# Microcontroller.net
KiCad netlist of a schematic drawn in Altium Designer
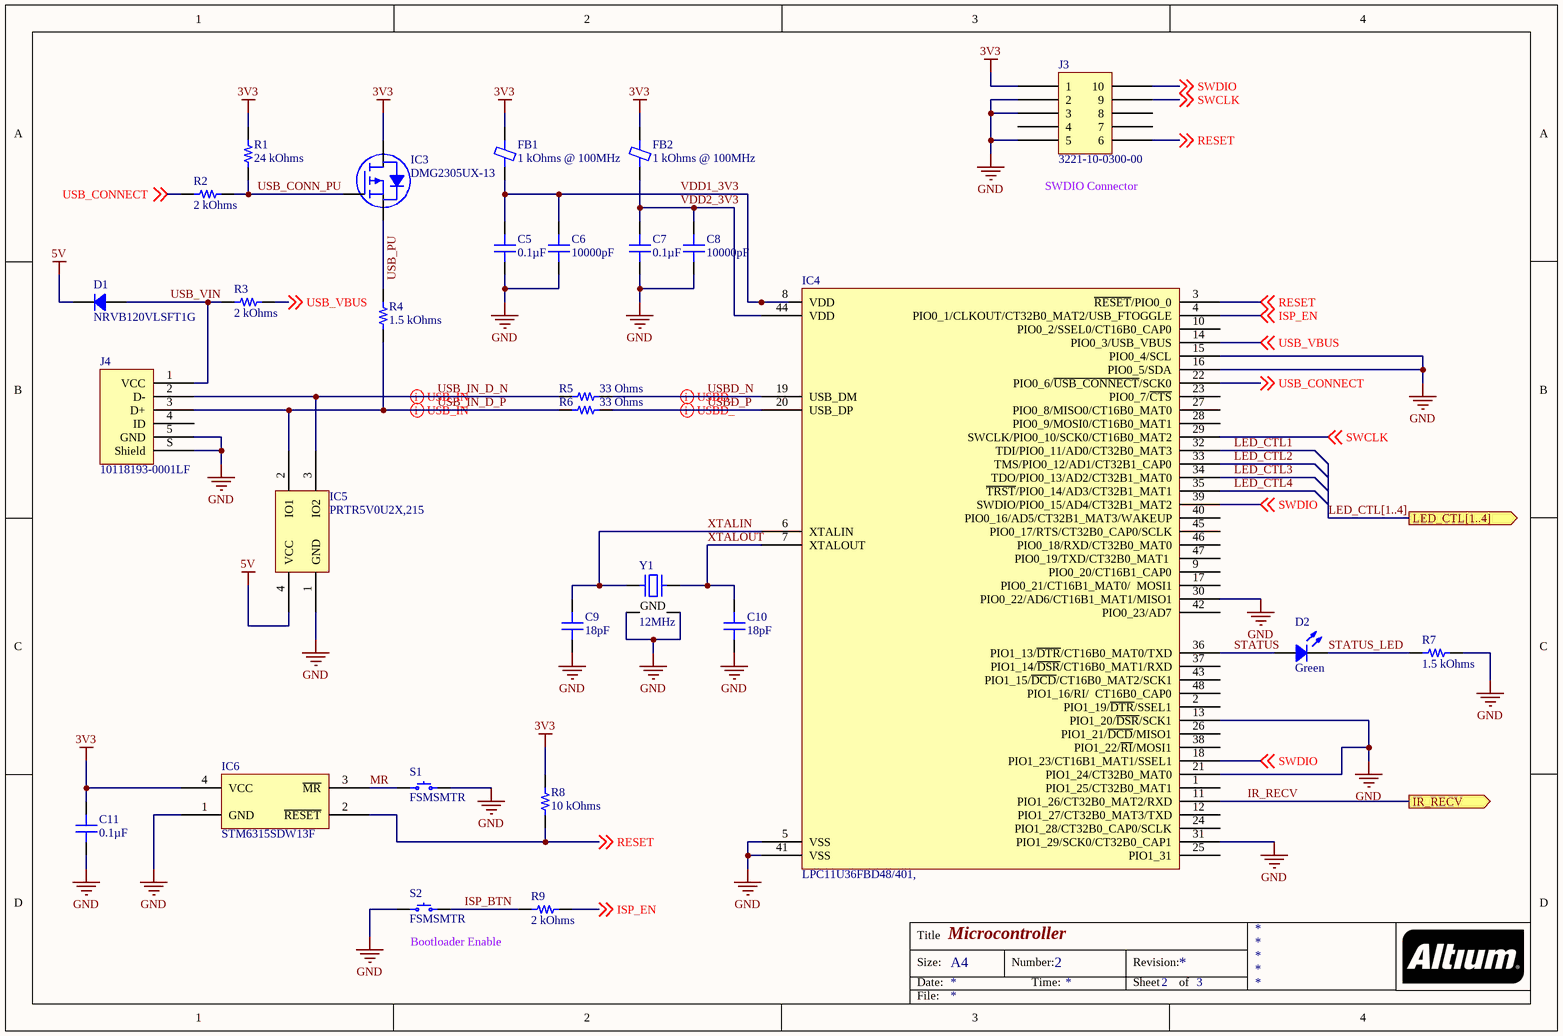
[diagram p0: Microcontroller.SchDoc]

(export (version "E")
  (design (tool "Eeschema 10.0.6"))
  (components
    (comp (ref "C5")
      (value "0.1µF")
      (footprint "CAP 0603_1608")
      (description "CAP CER 0.1UF 16V X7R 0603")
      (fields (field (name "PART NUMBER") "CS0603KRX7R7BB104") (field (name "MANUFACTURER") "Yageo"))
      (libsource (lib "Celestial Altium Library - altium_library") (part "Capacitor"))
    )
    (comp (ref "C6")
      (value "10000pF")
      (footprint "CAP 0603_1608")
      (description "CAP CER 10000PF 50V X7R 0603")
      (fields (field (name "PART NUMBER") "AC0603KPX7R9BB103") (field (name "MANUFACTURER") "Yageo"))
      (libsource (lib "Celestial Altium Library - altium_library") (part "Capacitor"))
    )
    (comp (ref "C7")
      (value "0.1µF")
      (footprint "CAP 0603_1608")
      (description "CAP CER 0.1UF 16V X7R 0603")
      (fields (field (name "PART NUMBER") "CS0603KRX7R7BB104") (field (name "MANUFACTURER") "Yageo"))
      (libsource (lib "Celestial Altium Library - altium_library") (part "Capacitor"))
    )
    (comp (ref "C8")
      (value "10000pF")
      (footprint "CAP 0603_1608")
      (description "CAP CER 10000PF 50V X7R 0603")
      (fields (field (name "PART NUMBER") "AC0603KPX7R9BB103") (field (name "MANUFACTURER") "Yageo"))
      (libsource (lib "Celestial Altium Library - altium_library") (part "Capacitor"))
    )
    (comp (ref "C9")
      (value "18pF")
      (footprint "CAP 0603_1608")
      (description "CAP CER 18PF 50V C0G/NP0 0603")
      (fields (field (name "PART NUMBER") "C0603C180K5GACTU") (field (name "MANUFACTURER") "KEMET"))
      (libsource (lib "Celestial Altium Library - altium_library") (part "Capacitor"))
    )
    (comp (ref "C10")
      (value "18pF")
      (footprint "CAP 0603_1608")
      (description "CAP CER 18PF 50V C0G/NP0 0603")
      (fields (field (name "PART NUMBER") "C0603C180K5GACTU") (field (name "MANUFACTURER") "KEMET"))
      (libsource (lib "Celestial Altium Library - altium_library") (part "Capacitor"))
    )
    (comp (ref "C11")
      (value "0.1µF")
      (footprint "CAP 0603_1608")
      (description "CAP CER 0.1UF 16V X7R 0603")
      (fields (field (name "PART NUMBER") "CS0603KRX7R7BB104") (field (name "MANUFACTURER") "Yageo"))
      (libsource (lib "Celestial Altium Library - altium_library") (part "Capacitor"))
    )
    (comp (ref "D1")
      (value "NRVB120VLSFT1G")
      (footprint "SOD123F")
      (description "DIODE SCHOTTKY 20V 1A SOD123")
      (fields (field (name "MANUFACTURER") "ON Semiconductor"))
      (libsource (lib "Celestial Altium Library - altium_library") (part "Diode"))
    )
    (comp (ref "D2")
      (value "Green")
      (footprint "LED 0603_1608 GREEN")
      (description "LED GREEN DIFFUSED 0603 SMD")
      (fields
        (field (name "PART NUMBER") "LG Q396-PS-35")
        (field (name "MANUFACTURER") "OSRAM Opto Semiconductors Inc.")
      )
      (libsource (lib "Celestial Altium Library - altium_library") (part "LED"))
    )
    (comp (ref "FB1")
      (value "1 kOhms @ 100MHz")
      (footprint "FER 0603_1608")
      (description "FERRITE BEAD,HIGH CURRENT, 0603")
      (fields (field (name "PART NUMBER") "FBTH1608HE102-T") (field (name "MANUFACTURER") "Taiyo Yuden"))
      (libsource (lib "Celestial Altium Library - altium_library") (part "Ferrite Chip"))
    )
    (comp (ref "FB2")
      (value "1 kOhms @ 100MHz")
      (footprint "FER 0603_1608")
      (description "FERRITE BEAD,HIGH CURRENT, 0603")
      (fields (field (name "PART NUMBER") "FBTH1608HE102-T") (field (name "MANUFACTURER") "Taiyo Yuden"))
      (libsource (lib "Celestial Altium Library - altium_library") (part "Ferrite Chip"))
    )
    (comp (ref "IC3")
      (value "DMG2305UX-13")
      (footprint "DIODES SOT-23-3")
      (description "MOSFET P-CH 20V 4.2A SOT23")
      (fields (field (name "MANUFACTURER") "Diodes Incorporated"))
      (libsource (lib "Celestial Altium Library - altium_library") (part "DIODES MOSFET P-CH SOT-23-3"))
    )
    (comp (ref "IC4")
      (value "LPC11U36FBD48/401,")
      (footprint "NXP LQFP-48 7X7MM")
      (description "IC MCU 32BIT 96KB FLASH 48LQFP")
      (fields (field (name "MANUFACTURER") "NXP USA Inc."))
      (libsource (lib "Celestial Altium Library - altium_library") (part "NXP LPC11U3X LQFP48"))
    )
    (comp (ref "IC5")
      (value "PRTR5V0U2X,215")
      (footprint "SOT143B")
      (description "TVS DIODE 5.5V SOT143B")
      (fields (field (name "MANUFACTURER") "Nexperia USA Inc."))
      (libsource (lib "Celestial Altium Library - altium_library") (part "NXP PRTR5V0U2X"))
    )
    (comp (ref "IC6")
      (value "STM6315SDW13F")
      (footprint "ST SOT-143-4")
      (description "IC SUPERVISOR 1 CHANNEL SOT143-4")
      (fields (field (name "MANUFACTURER") "STMicroelectronics"))
      (libsource (lib "Celestial Altium Library - altium_library") (part "ST STM3615"))
    )
    (comp (ref "J3")
      (value "3221-10-0300-00")
      (footprint "CNC TECH 3221-10-0300-00")
      (description "CONN HEADER SMD 10POS 1.27MM")
      (fields (field (name "MANUFACTURER") "CNC Tech"))
      (libsource (lib "Celestial Altium Library - altium_library") (part "2x5 Pin"))
    )
    (comp (ref "J4")
      (value "10118193-0001LF")
      (footprint "FCI USB 10118193-0001LF")
      (description "CONN RCPT USB2.0 MICRO B SMD R/A")
      (fields (field (name "MANUFACTURER") "Amphenol ICC (FCI)"))
      (libsource (lib "Celestial Altium Library - altium_library") (part "USB 2.0 Type B Micro"))
    )
    (comp (ref "R1")
      (value "24 kOhms")
      (footprint "RES 0603_1608")
      (description "RES SMD 24K OHM 1% 1/10W 0603")
      (fields
        (field (name "PART NUMBER") "ERJ-3EKF2402V")
        (field (name "MANUFACTURER") "Panasonic Electronic Components")
      )
      (libsource (lib "Celestial Altium Library - altium_library") (part "Resistor"))
    )
    (comp (ref "R2")
      (value "2 kOhms")
      (footprint "RES 0603_1608")
      (description "RES SMD 2K OHM 1% 1/10W 0603")
      (fields
        (field (name "PART NUMBER") "ERJ-3EKF2001V")
        (field (name "MANUFACTURER") "Panasonic Electronic Components")
      )
      (libsource (lib "Celestial Altium Library - altium_library") (part "Resistor"))
    )
    (comp (ref "R3")
      (value "2 kOhms")
      (footprint "RES 0603_1608")
      (description "RES SMD 2K OHM 5% 1/4W 0603")
      (fields
        (field (name "PART NUMBER") "ERJ-PA3J202V")
        (field (name "MANUFACTURER") "Panasonic Electronic Components")
      )
      (libsource (lib "Celestial Altium Library - altium_library") (part "Resistor"))
    )
    (comp (ref "R4")
      (value "1.5 kOhms")
      (footprint "RES 0603_1608")
      (description "RES SMD 1.5K OHM 1% 1/10W 0603")
      (fields
        (field (name "PART NUMBER") "ERJ-3EKF1501V")
        (field (name "MANUFACTURER") "Panasonic Electronic Components")
      )
      (libsource (lib "Celestial Altium Library - altium_library") (part "Resistor"))
    )
    (comp (ref "R5")
      (value "33 Ohms")
      (footprint "RES 0603_1608")
      (description "RES SMD 33 OHM 1% 1/10W 0603")
      (fields
        (field (name "PART NUMBER") "ERJ-3EKF33R0V")
        (field (name "MANUFACTURER") "Panasonic Electronic Components")
      )
      (libsource (lib "Celestial Altium Library - altium_library") (part "Resistor"))
    )
    (comp (ref "R6")
      (value "33 Ohms")
      (footprint "RES 0603_1608")
      (description "RES SMD 33 OHM 1% 1/10W 0603")
      (fields
        (field (name "PART NUMBER") "ERJ-3EKF33R0V")
        (field (name "MANUFACTURER") "Panasonic Electronic Components")
      )
      (libsource (lib "Celestial Altium Library - altium_library") (part "Resistor"))
    )
    (comp (ref "R7")
      (value "1.5 kOhms")
      (footprint "RES 0603_1608")
      (description "RES SMD 1.5K OHM 1% 1/10W 0603")
      (fields
        (field (name "PART NUMBER") "ERJ-3EKF1501V")
        (field (name "MANUFACTURER") "Panasonic Electronic Components")
      )
      (libsource (lib "Celestial Altium Library - altium_library") (part "Resistor"))
    )
    (comp (ref "R8")
      (value "10 kOhms")
      (footprint "RES 0603_1608")
      (description "RES SMD 10K OHM 1% 1/10W 0603")
      (fields
        (field (name "PART NUMBER") "ERJ-3EKF1002V")
        (field (name "MANUFACTURER") "Panasonic Electronic Components")
      )
      (libsource (lib "Celestial Altium Library - altium_library") (part "Resistor"))
    )
    (comp (ref "R9")
      (value "2 kOhms")
      (footprint "RES 0603_1608")
      (description "RES SMD 2K OHM 5% 1/4W 0603")
      (fields
        (field (name "PART NUMBER") "ERJ-PA3J202V")
        (field (name "MANUFACTURER") "Panasonic Electronic Components")
      )
      (libsource (lib "Celestial Altium Library - altium_library") (part "Resistor"))
    )
    (comp (ref "S1")
      (value "FSMSMTR")
      (footprint "TE FSMSMTR")
      (description "SWITCH TACTILE SPST-NO 0.05A 24V")
      (fields (field (name "MANUFACTURER") "TE Connectivity ALCOSWITCH Switches"))
      (libsource (lib "Celestial Altium Library - altium_library") (part "SPST-NO 2 PIN"))
    )
    (comp (ref "S2")
      (value "FSMSMTR")
      (footprint "TE FSMSMTR")
      (description "SWITCH TACTILE SPST-NO 0.05A 24V")
      (fields (field (name "MANUFACTURER") "TE Connectivity ALCOSWITCH Switches"))
      (libsource (lib "Celestial Altium Library - altium_library") (part "SPST-NO 2 PIN"))
    )
    (comp (ref "Y1")
      (value "12MHz")
      (footprint "ABRACON ABM8G")
      (description "IOT 12MHZ 10PF XTAL")
      (fields
        (field (name "PART NUMBER") "ABM8G-106-12.000MHZ-T")
        (field (name "MANUFACTURER") "Abracon LLC")
      )
      (libsource (lib "Celestial Altium Library - altium_library") (part "Abracon Crystal ABM8G"))
    )
  )
  (nets
    (net (code "1") (name "/IR_RECV") (class "Default")
      (node (ref "IC4") (pin "11") (pinfunction "PIO1_26/CT32B0_MAT2/RXD_11") (pintype "passive"))
    )
    (net (code "2") (name "/ISP_BTN") (class "Default")
      (node (ref "R9") (pin "1") (pinfunction "1_1") (pintype "passive"))
      (node (ref "S2") (pin "2") (pinfunction "2_2") (pintype "passive"))
    )
    (net (code "3") (name "/LED_CTL1") (class "Default")
      (node (ref "IC4") (pin "32") (pinfunction "TDI/PIO0_11/AD0/CT32B0_MAT3_32") (pintype "passive"))
    )
    (net (code "4") (name "/LED_CTL2") (class "Default")
      (node (ref "IC4") (pin "33") (pinfunction "TMS/PIO0_12/AD1/CT32B1_CAP0_33") (pintype "passive"))
    )
    (net (code "5") (name "/LED_CTL3") (class "Default")
      (node (ref "IC4") (pin "34") (pinfunction "TDO/PIO0_13/AD2/CT32B1_MAT0_34") (pintype "passive"))
    )
    (net (code "6") (name "/LED_CTL4") (class "Default")
      (node (ref "IC4") (pin "35") (pinfunction "~{TRST}/PIO0_14/AD3/CT32B1_MAT1_35") (pintype "passive"))
    )
    (net (code "8") (name "/MR") (class "Default")
      (node (ref "IC6") (pin "3") (pinfunction "~{MR}_3") (pintype "passive"))
      (node (ref "S1") (pin "1") (pinfunction "1_1") (pintype "passive"))
    )
    (net (code "9") (name "/STATUS") (class "Default")
      (node (ref "D2") (pin "1") (pinfunction "1_1") (pintype "passive"))
      (node (ref "IC4") (pin "36") (pinfunction "PIO1_13/~{DTR}/CT16B0_MAT0/TXD_36") (pintype "passive"))
    )
    (net (code "10") (name "/STATUS_LED") (class "Default")
      (node (ref "D2") (pin "2") (pinfunction "2_2") (pintype "passive"))
      (node (ref "R7") (pin "2") (pinfunction "2_2") (pintype "passive"))
    )
    (net (code "11") (name "/USBD_N") (class "Default")
      (node (ref "IC4") (pin "19") (pinfunction "USB_DM_19") (pintype "passive"))
      (node (ref "R5") (pin "2") (pinfunction "2_2") (pintype "passive"))
    )
    (net (code "12") (name "/USBD_P") (class "Default")
      (node (ref "IC4") (pin "20") (pinfunction "USB_DP_20") (pintype "passive"))
      (node (ref "R6") (pin "2") (pinfunction "2_2") (pintype "passive"))
    )
    (net (code "13") (name "/USB_CONN_PU") (class "Default")
      (node (ref "IC3") (pin "1") (pinfunction "G_1") (pintype "passive"))
      (node (ref "R1") (pin "1") (pinfunction "1_1") (pintype "passive"))
      (node (ref "R2") (pin "2") (pinfunction "2_2") (pintype "passive"))
    )
    (net (code "14") (name "/USB_IN_D_N") (class "Default")
      (node (ref "IC5") (pin "3") (pinfunction "IO2_3") (pintype "passive"))
      (node (ref "J4") (pin "2") (pinfunction "D-_2") (pintype "passive"))
      (node (ref "R5") (pin "1") (pinfunction "1_1") (pintype "passive"))
    )
    (net (code "15") (name "/USB_IN_D_P") (class "Default")
      (node (ref "IC5") (pin "2") (pinfunction "IO1_2") (pintype "passive"))
      (node (ref "J4") (pin "3") (pinfunction "D+_3") (pintype "passive"))
      (node (ref "R4") (pin "1") (pinfunction "1_1") (pintype "passive"))
      (node (ref "R6") (pin "1") (pinfunction "1_1") (pintype "passive"))
    )
    (net (code "16") (name "/USB_PU") (class "Default")
      (node (ref "IC3") (pin "2") (pinfunction "S_2") (pintype "passive"))
      (node (ref "R4") (pin "2") (pinfunction "2_2") (pintype "passive"))
    )
    (net (code "17") (name "/USB_VIN") (class "Default")
      (node (ref "D1") (pin "1") (pinfunction "1_1") (pintype "passive"))
      (node (ref "J4") (pin "1") (pinfunction "VCC_1") (pintype "passive"))
      (node (ref "R3") (pin "1") (pinfunction "1_1") (pintype "passive"))
    )
    (net (code "18") (name "/VDD1_3V3") (class "Default")
      (node (ref "C5") (pin "2") (pinfunction "2_2") (pintype "passive"))
      (node (ref "C6") (pin "2") (pinfunction "2_2") (pintype "passive"))
      (node (ref "FB1") (pin "1") (pinfunction "1_1") (pintype "passive"))
      (node (ref "IC4") (pin "8") (pinfunction "VDD_8") (pintype "passive"))
    )
    (net (code "19") (name "/VDD2_3V3") (class "Default")
      (node (ref "C7") (pin "2") (pinfunction "2_2") (pintype "passive"))
      (node (ref "C8") (pin "2") (pinfunction "2_2") (pintype "passive"))
      (node (ref "FB2") (pin "1") (pinfunction "1_1") (pintype "passive"))
      (node (ref "IC4") (pin "44") (pinfunction "VDD_44") (pintype "passive"))
    )
    (net (code "20") (name "/XTALIN") (class "Default")
      (node (ref "C9") (pin "2") (pinfunction "2_2") (pintype "passive"))
      (node (ref "IC4") (pin "6") (pinfunction "XTALIN_6") (pintype "passive"))
      (node (ref "Y1") (pin "1") (pinfunction "1_1") (pintype "passive"))
    )
    (net (code "21") (name "/XTALOUT") (class "Default")
      (node (ref "C10") (pin "2") (pinfunction "2_2") (pintype "passive"))
      (node (ref "IC4") (pin "7") (pinfunction "XTALOUT_7") (pintype "passive"))
      (node (ref "Y1") (pin "3") (pinfunction "3_3") (pintype "passive"))
    )
    (net (code "22") (name "3V3") (class "Default")
      (node (ref "C11") (pin "2") (pinfunction "2_2") (pintype "passive"))
      (node (ref "FB1") (pin "2") (pinfunction "2_2") (pintype "passive"))
      (node (ref "FB2") (pin "2") (pinfunction "2_2") (pintype "passive"))
      (node (ref "IC3") (pin "3") (pinfunction "D_3") (pintype "passive"))
      (node (ref "IC6") (pin "4") (pinfunction "VCC_4") (pintype "passive"))
      (node (ref "J3") (pin "1") (pinfunction "1_1") (pintype "passive"))
      (node (ref "R1") (pin "2") (pinfunction "2_2") (pintype "passive"))
      (node (ref "R8") (pin "2") (pinfunction "2_2") (pintype "passive"))
    )
    (net (code "23") (name "5V") (class "Default")
      (node (ref "D1") (pin "2") (pinfunction "2_2") (pintype "passive"))
      (node (ref "IC5") (pin "4") (pinfunction "VCC_4") (pintype "passive"))
    )
    (net (code "24") (name "GND") (class "Default")
      (node (ref "C10") (pin "1") (pinfunction "1_1") (pintype "passive"))
      (node (ref "C11") (pin "1") (pinfunction "1_1") (pintype "passive"))
      (node (ref "C5") (pin "1") (pinfunction "1_1") (pintype "passive"))
      (node (ref "C6") (pin "1") (pinfunction "1_1") (pintype "passive"))
      (node (ref "C7") (pin "1") (pinfunction "1_1") (pintype "passive"))
      (node (ref "C8") (pin "1") (pinfunction "1_1") (pintype "passive"))
      (node (ref "C9") (pin "1") (pinfunction "1_1") (pintype "passive"))
      (node (ref "IC4") (pin "13") (pinfunction "PIO1_20/~{DSR}/SCK1_13") (pintype "passive"))
      (node (ref "IC4") (pin "15") (pinfunction "PIO0_4/SCL_15") (pintype "passive"))
      (node (ref "IC4") (pin "16") (pinfunction "PIO0_5/SDA_16") (pintype "passive"))
      (node (ref "IC4") (pin "21") (pinfunction "PIO1_24/CT32B0_MAT0_21") (pintype "passive"))
      (node (ref "IC4") (pin "30") (pinfunction "PIO0_22/AD6/CT16B1_MAT1/MISO1_30") (pintype "passive"))
      (node (ref "IC4") (pin "31") (pinfunction "PIO1_29/SCK0/CT32B0_CAP1_31") (pintype "passive"))
      (node (ref "IC4") (pin "41") (pinfunction "VSS_41") (pintype "passive"))
      (node (ref "IC4") (pin "5") (pinfunction "VSS_5") (pintype "passive"))
      (node (ref "IC5") (pin "1") (pinfunction "GND_1") (pintype "passive"))
      (node (ref "IC6") (pin "1") (pinfunction "GND_1") (pintype "passive"))
      (node (ref "J3") (pin "2") (pinfunction "2_2") (pintype "passive"))
      (node (ref "J3") (pin "3") (pinfunction "3_3") (pintype "passive"))
      (node (ref "J3") (pin "5") (pinfunction "5_5") (pintype "passive"))
      (node (ref "J4") (pin "5") (pinfunction "GND_5") (pintype "passive"))
      (node (ref "J4") (pin "S") (pinfunction "Shield_S") (pintype "passive"))
      (node (ref "R7") (pin "1") (pinfunction "1_1") (pintype "passive"))
      (node (ref "S1") (pin "2") (pinfunction "2_2") (pintype "passive"))
      (node (ref "S2") (pin "1") (pinfunction "1_1") (pintype "passive"))
      (node (ref "Y1") (pin "2") (pinfunction "GND_2") (pintype "passive"))
      (node (ref "Y1") (pin "4") (pinfunction "GND_4") (pintype "passive"))
    )
    (net (code "25") (name "ISP_EN") (class "Default")
      (node (ref "IC4") (pin "4") (pinfunction "PIO0_1/CLKOUT/CT32B0_MAT2/USB_FTOGGLE_4") (pintype "passive"))
      (node (ref "R9") (pin "2") (pinfunction "2_2") (pintype "passive"))
    )
    (net (code "26") (name "RESET") (class "Default")
      (node (ref "IC4") (pin "3") (pinfunction "~{RESET}/PIO0_0_3") (pintype "passive"))
      (node (ref "IC6") (pin "2") (pinfunction "~{RESET}_2") (pintype "passive"))
      (node (ref "J3") (pin "6") (pinfunction "6_6") (pintype "passive"))
      (node (ref "R8") (pin "1") (pinfunction "1_1") (pintype "passive"))
    )
    (net (code "27") (name "SWCLK") (class "Default")
      (node (ref "IC4") (pin "29") (pinfunction "SWCLK/PIO0_10/SCK0/CT16B0_MAT2_29") (pintype "passive"))
      (node (ref "J3") (pin "9") (pinfunction "9_9") (pintype "passive"))
    )
    (net (code "28") (name "SWDIO") (class "Default")
      (node (ref "IC4") (pin "18") (pinfunction "PIO1_23/CT16B1_MAT1/SSEL1_18") (pintype "passive"))
      (node (ref "IC4") (pin "39") (pinfunction "SWDIO/PIO0_15/AD4/CT32B1_MAT2_39") (pintype "passive"))
      (node (ref "J3") (pin "10") (pinfunction "10_10") (pintype "passive"))
    )
    (net (code "29") (name "USB_CONNECT") (class "Default")
      (node (ref "IC4") (pin "22") (pinfunction "PIO0_6/~{USB_CONNECT}/SCK0_22") (pintype "passive"))
      (node (ref "R2") (pin "1") (pinfunction "1_1") (pintype "passive"))
    )
    (net (code "30") (name "USB_VBUS") (class "Default")
      (node (ref "IC4") (pin "14") (pinfunction "PIO0_3/USB_VBUS_14") (pintype "passive"))
      (node (ref "R3") (pin "2") (pinfunction "2_2") (pintype "passive"))
    )
    (net (code "31") (name "unconnected-(IC4-PIO0_2{slash}SSEL0{slash}CT16B0_CAP0-Pad10)") (class "Default")
      (node (ref "IC4") (pin "10") (pinfunction "PIO0_2/SSEL0/CT16B0_CAP0_10") (pintype "passive"))
    )
    (net (code "32") (name "unconnected-(IC4-PIO0_7{slash}~{CTS}-Pad23)") (class "Default")
      (node (ref "IC4") (pin "23") (pinfunction "PIO0_7/~{CTS}_23") (pintype "passive"))
    )
    (net (code "33") (name "unconnected-(IC4-PIO0_8{slash}MISO0{slash}CT16B0_MAT0-Pad27)") (class "Default")
      (node (ref "IC4") (pin "27") (pinfunction "PIO0_8/MISO0/CT16B0_MAT0_27") (pintype "passive"))
    )
    (net (code "34") (name "unconnected-(IC4-PIO0_9{slash}MOSI0{slash}CT16B0_MAT1-Pad28)") (class "Default")
      (node (ref "IC4") (pin "28") (pinfunction "PIO0_9/MOSI0/CT16B0_MAT1_28") (pintype "passive"))
    )
    (net (code "35") (name "unconnected-(IC4-PIO0_16{slash}AD5{slash}CT32B1_MAT3{slash}WAKEUP-Pad40)") (class "Default")
      (node (ref "IC4") (pin "40") (pinfunction "PIO0_16/AD5/CT32B1_MAT3/WAKEUP_40") (pintype "passive"))
    )
    (net (code "36") (name "unconnected-(IC4-PIO0_17{slash}RTS{slash}CT32B0_CAP0{slash}SCLK-Pad45)") (class "Default")
      (node (ref "IC4") (pin "45") (pinfunction "PIO0_17/RTS/CT32B0_CAP0/SCLK_45") (pintype "passive"))
    )
    (net (code "37") (name "unconnected-(IC4-PIO0_18{slash}RXD{slash}CT32B0_MAT0-Pad46)") (class "Default")
      (node (ref "IC4") (pin "46") (pinfunction "PIO0_18/RXD/CT32B0_MAT0_46") (pintype "passive"))
    )
    (net (code "38") (name "unconnected-(IC4-PIO0_19{slash}TXD{slash}CT32B0_MAT1-Pad47)") (class "Default")
      (node (ref "IC4") (pin "47") (pinfunction "PIO0_19/TXD/CT32B0_MAT1_47") (pintype "passive"))
    )
    (net (code "39") (name "unconnected-(IC4-PIO0_20{slash}CT16B1_CAP0-Pad9)") (class "Default")
      (node (ref "IC4") (pin "9") (pinfunction "PIO0_20/CT16B1_CAP0_9") (pintype "passive"))
    )
    (net (code "40") (name "unconnected-(IC4-PIO0_21{slash}CT16B1_MAT0{slash}__MOSI1-Pad17)") (class "Default")
      (node (ref "IC4") (pin "17") (pinfunction "PIO0_21/CT16B1_MAT0/__MOSI1_17") (pintype "passive"))
    )
    (net (code "41") (name "unconnected-(IC4-PIO0_23{slash}AD7-Pad42)") (class "Default")
      (node (ref "IC4") (pin "42") (pinfunction "PIO0_23/AD7_42") (pintype "passive"))
    )
    (net (code "42") (name "unconnected-(IC4-PIO1_14{slash}~{DSR}{slash}CT16B0_MAT1{slash}RXD-Pad37)") (class "Default")
      (node (ref "IC4") (pin "37") (pinfunction "PIO1_14/~{DSR}/CT16B0_MAT1/RXD_37") (pintype "passive"))
    )
    (net (code "43") (name "unconnected-(IC4-PIO1_15{slash}~{DCD}{slash}CT16B0_MAT2{slash}SCK1-Pad43)") (class "Default")
      (node (ref "IC4") (pin "43") (pinfunction "PIO1_15/~{DCD}/CT16B0_MAT2/SCK1_43") (pintype "passive"))
    )
    (net (code "44") (name "unconnected-(IC4-PIO1_16{slash}RI{slash}__CT16B0_CAP0-Pad48)") (class "Default")
      (node (ref "IC4") (pin "48") (pinfunction "PIO1_16/RI/__CT16B0_CAP0_48") (pintype "passive"))
    )
    (net (code "45") (name "unconnected-(IC4-PIO1_19{slash}~{DTR}{slash}SSEL1-Pad2)") (class "Default")
      (node (ref "IC4") (pin "2") (pinfunction "PIO1_19/~{DTR}/SSEL1_2") (pintype "passive"))
    )
    (net (code "46") (name "unconnected-(IC4-PIO1_21{slash}~{DCD}{slash}MISO1-Pad26)") (class "Default")
      (node (ref "IC4") (pin "26") (pinfunction "PIO1_21/~{DCD}/MISO1_26") (pintype "passive"))
    )
    (net (code "47") (name "unconnected-(IC4-PIO1_22{slash}~{RI}{slash}MOSI1-Pad38)") (class "Default")
      (node (ref "IC4") (pin "38") (pinfunction "PIO1_22/~{RI}/MOSI1_38") (pintype "passive"))
    )
    (net (code "48") (name "unconnected-(IC4-PIO1_25{slash}CT32B0_MAT1-Pad1)") (class "Default")
      (node (ref "IC4") (pin "1") (pinfunction "PIO1_25/CT32B0_MAT1_1") (pintype "passive"))
    )
    (net (code "49") (name "unconnected-(IC4-PIO1_27{slash}CT32B0_MAT3{slash}TXD-Pad12)") (class "Default")
      (node (ref "IC4") (pin "12") (pinfunction "PIO1_27/CT32B0_MAT3/TXD_12") (pintype "passive"))
    )
    (net (code "50") (name "unconnected-(IC4-PIO1_28{slash}CT32B0_CAP0{slash}SCLK-Pad24)") (class "Default")
      (node (ref "IC4") (pin "24") (pinfunction "PIO1_28/CT32B0_CAP0/SCLK_24") (pintype "passive"))
    )
    (net (code "51") (name "unconnected-(IC4-PIO1_31-Pad25)") (class "Default")
      (node (ref "IC4") (pin "25") (pinfunction "PIO1_31_25") (pintype "passive"))
    )
    (net (code "52") (name "unconnected-(J3-Pad4)") (class "Default")
      (node (ref "J3") (pin "4") (pinfunction "4_4") (pintype "passive"))
    )
    (net (code "53") (name "unconnected-(J3-Pad7)") (class "Default")
      (node (ref "J3") (pin "7") (pinfunction "7_7") (pintype "passive"))
    )
    (net (code "54") (name "unconnected-(J3-Pad8)") (class "Default")
      (node (ref "J3") (pin "8") (pinfunction "8_8") (pintype "passive"))
    )
    (net (code "55") (name "unconnected-(J4-ID-Pad4)") (class "Default")
      (node (ref "J4") (pin "4") (pinfunction "ID_4") (pintype "passive"))
    )
  )
)
